# Power.net
KiCad netlist of a schematic drawn in Altium Designer
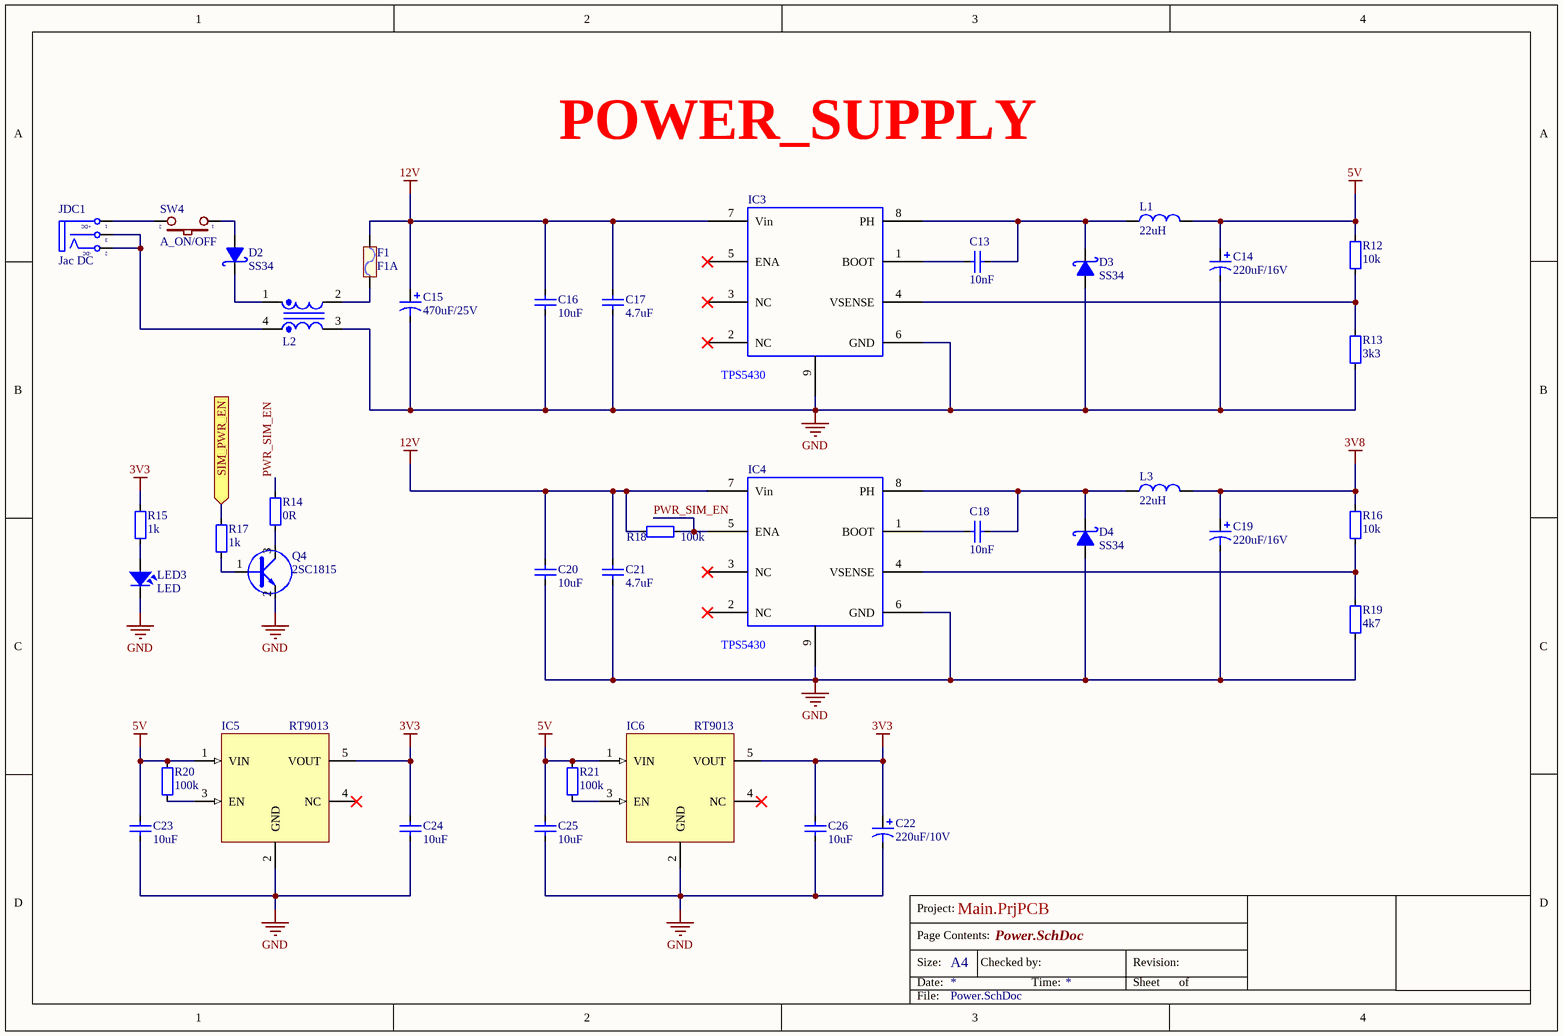
[diagram p0: Power.SchDoc]

(export (version "E")
  (design (tool "Eeschema 10.0.6"))
  (components
    (comp (ref "C13")
      (value "10nF")
      (footprint "CAP_0805")
      (description "Capacitor")
      (fields (field (name "PUBLISHER") "Altium Limited"))
      (libsource (lib "My Library") (part "CapSMD"))
    )
    (comp (ref "C14")
      (value "220uF/16V")
      (footprint "C8mm")
      (description "Polarized Capacitor (Axial)")
      (fields (field (name "PUBLISHER") "Altium Limited"))
      (libsource (lib "My Library") (part "Cap Pol"))
    )
    (comp (ref "C15")
      (value "470uF/25V")
      (footprint "C8mm")
      (description "Polarized Capacitor (Axial)")
      (fields (field (name "PUBLISHER") "Altium Limited"))
      (libsource (lib "My Library") (part "Cap Pol"))
    )
    (comp (ref "C16")
      (value "10uF")
      (footprint "CAP_0805")
      (description "Capacitor")
      (fields (field (name "PUBLISHER") "Altium Limited"))
      (libsource (lib "My Library") (part "CapSMD"))
    )
    (comp (ref "C17")
      (value "4.7uF")
      (footprint "CAP_0805")
      (description "Capacitor")
      (fields (field (name "PUBLISHER") "Altium Limited"))
      (libsource (lib "My Library") (part "CapSMD"))
    )
    (comp (ref "C18")
      (value "10nF")
      (footprint "CAP_0805")
      (description "Capacitor")
      (fields (field (name "PUBLISHER") "Altium Limited"))
      (libsource (lib "My Library") (part "CapSMD"))
    )
    (comp (ref "C19")
      (value "220uF/16V")
      (footprint "C8mm")
      (description "Polarized Capacitor (Axial)")
      (fields (field (name "PUBLISHER") "Altium Limited"))
      (libsource (lib "My Library") (part "Cap Pol"))
    )
    (comp (ref "C20")
      (value "10uF")
      (footprint "CAP_0805")
      (description "Capacitor")
      (fields (field (name "PUBLISHER") "Altium Limited"))
      (libsource (lib "My Library") (part "CapSMD"))
    )
    (comp (ref "C21")
      (value "4.7uF")
      (footprint "CAP_0805")
      (description "Capacitor")
      (fields (field (name "PUBLISHER") "Altium Limited"))
      (libsource (lib "My Library") (part "CapSMD"))
    )
    (comp (ref "C22")
      (value "220uF/10V")
      (footprint "C8mm")
      (description "Polarized Capacitor (Axial)")
      (fields (field (name "PUBLISHER") "Altium Limited"))
      (libsource (lib "My Library") (part "Cap Pol"))
    )
    (comp (ref "C23")
      (value "10uF")
      (footprint "CAP_0805")
      (description "Capacitor")
      (fields (field (name "PUBLISHER") "Altium Limited"))
      (libsource (lib "My Library") (part "CapSMD"))
    )
    (comp (ref "C24")
      (value "10uF")
      (footprint "CAP_0805")
      (description "Capacitor")
      (fields (field (name "PUBLISHER") "Altium Limited"))
      (libsource (lib "My Library") (part "CapSMD"))
    )
    (comp (ref "C25")
      (value "10uF")
      (footprint "CAP_0805")
      (description "Capacitor")
      (fields (field (name "PUBLISHER") "Altium Limited"))
      (libsource (lib "My Library") (part "CapSMD"))
    )
    (comp (ref "C26")
      (value "10uF")
      (footprint "CAP_0805")
      (description "Capacitor")
      (fields (field (name "PUBLISHER") "Altium Limited"))
      (libsource (lib "My Library") (part "CapSMD"))
    )
    (comp (ref "D2")
      (value "SS34")
      (footprint "DO-214AC(SMA)")
      (description "Diode Schottky SS34")
      (libsource (lib "My Library") (part "Diode Schottky"))
    )
    (comp (ref "D3")
      (value "SS34")
      (footprint "DO-214AC(SMA)")
      (description "Diode Schottky SS34")
      (libsource (lib "My Library") (part "Diode Schottky"))
    )
    (comp (ref "D4")
      (value "SS34")
      (footprint "DO-214AC(SMA)")
      (description "Diode Schottky SS34")
      (libsource (lib "My Library") (part "Diode Schottky"))
    )
    (comp (ref "F1")
      (value "F1A")
      (footprint "FUSE2C")
      (description "Fuse RUEF300 30V 3A")
      (fields (field (name "DESIGNED BY") "VanDungEvn"))
      (libsource (lib "My Library") (part "Fuse"))
    )
    (comp (ref "IC3")
      (value "TPS5430")
      (footprint "TPS5430-2")
      (fields (field (name "NAME") "TPS5430"))
      (libsource (lib "My Library") (part "TPS5430"))
    )
    (comp (ref "IC4")
      (value "TPS5430")
      (footprint "TPS5430-2")
      (fields (field (name "NAME") "TPS5430"))
      (libsource (lib "My Library") (part "TPS5430"))
    )
    (comp (ref "IC5")
      (value "RT9013")
      (footprint "SOT23-5")
      (description "RT9013-33GB IC REG LINEAR 3.3V 500mA SOT23-5")
      (libsource (lib "My Library") (part "RT9013"))
    )
    (comp (ref "IC6")
      (value "RT9013")
      (footprint "SOT23-5")
      (description "RT9013-33GB IC REG LINEAR 3.3V 500mA SOT23-5")
      (libsource (lib "My Library") (part "RT9013"))
    )
    (comp (ref "JDC1")
      (value "Jac DC")
      (footprint "DC-IN")
      (description "Jac DC input")
      (libsource (lib "My Library") (part "DCIN"))
    )
    (comp (ref "L1")
      (value "22uH")
      (footprint "L-SMD-M-7.3x4.5")
      (description "Inductor")
      (libsource (lib "My Library") (part "Inductor"))
    )
    (comp (ref "L2")
      (value "Inductor Filter")
      (footprint "EE8.3")
      (fields (field (name "DESIGNED BY") "VanDungEvn"))
      (libsource (lib "My Library") (part "L_Filter"))
    )
    (comp (ref "L3")
      (value "22uH")
      (footprint "L-SMD-M-7.3x4.5")
      (description "Inductor")
      (libsource (lib "My Library") (part "Inductor"))
    )
    (comp (ref "LED3")
      (value "LED")
      (footprint "LED-0805-Red")
      (description "LED Single colour Green and Red")
      (libsource (lib "My Library") (part "LED"))
    )
    (comp (ref "Q4")
      (value "2SC1815")
      (footprint "SOT23D")
      (description "NPN 600mW, ECB")
      (libsource (lib "My Library") (part "C1815"))
    )
    (comp (ref "R12")
      (value "10k")
      (footprint "RES-SMD-0805")
      (description "Resistor")
      (fields
        (field (name "MANUFACTURER") "Generic Components")
        (field (name "PUBLISHER") "Altium Hobart Technology Centre")
      )
      (libsource (lib "My Library") (part "Resistor - SMD"))
    )
    (comp (ref "R13")
      (value "3k3")
      (footprint "RES-SMD-0805")
      (description "Resistor")
      (fields
        (field (name "MANUFACTURER") "Generic Components")
        (field (name "PUBLISHER") "Altium Hobart Technology Centre")
      )
      (libsource (lib "My Library") (part "Resistor - SMD"))
    )
    (comp (ref "R14")
      (value "0R")
      (footprint "RES-SMD-0805")
      (description "Resistor")
      (fields
        (field (name "MANUFACTURER") "Generic Components")
        (field (name "PUBLISHER") "Altium Hobart Technology Centre")
      )
      (libsource (lib "My Library") (part "Resistor - SMD"))
    )
    (comp (ref "R15")
      (value "1k")
      (footprint "RES-SMD-0805")
      (description "Resistor")
      (fields
        (field (name "MANUFACTURER") "Generic Components")
        (field (name "PUBLISHER") "Altium Hobart Technology Centre")
      )
      (libsource (lib "My Library") (part "Resistor - SMD"))
    )
    (comp (ref "R16")
      (value "10k")
      (footprint "RES-SMD-0805")
      (description "Resistor")
      (fields
        (field (name "MANUFACTURER") "Generic Components")
        (field (name "PUBLISHER") "Altium Hobart Technology Centre")
      )
      (libsource (lib "My Library") (part "Resistor - SMD"))
    )
    (comp (ref "R17")
      (value "1k")
      (footprint "RES-SMD-0805")
      (description "Resistor")
      (fields
        (field (name "MANUFACTURER") "Generic Components")
        (field (name "PUBLISHER") "Altium Hobart Technology Centre")
      )
      (libsource (lib "My Library") (part "Resistor - SMD"))
    )
    (comp (ref "R18")
      (value "100k")
      (footprint "RES-SMD-0805")
      (description "Resistor")
      (fields
        (field (name "MANUFACTURER") "Generic Components")
        (field (name "PUBLISHER") "Altium Hobart Technology Centre")
      )
      (libsource (lib "My Library") (part "Resistor - SMD"))
    )
    (comp (ref "R19")
      (value "4k7")
      (footprint "RES-SMD-0805")
      (description "Resistor")
      (fields
        (field (name "MANUFACTURER") "Generic Components")
        (field (name "PUBLISHER") "Altium Hobart Technology Centre")
      )
      (libsource (lib "My Library") (part "Resistor - SMD"))
    )
    (comp (ref "R20")
      (value "100k")
      (footprint "RES-SMD-0805")
      (description "Resistor")
      (fields
        (field (name "MANUFACTURER") "Generic Components")
        (field (name "PUBLISHER") "Altium Hobart Technology Centre")
      )
      (libsource (lib "My Library") (part "Resistor - SMD"))
    )
    (comp (ref "R21")
      (value "100k")
      (footprint "RES-SMD-0805")
      (description "Resistor")
      (fields
        (field (name "MANUFACTURER") "Generic Components")
        (field (name "PUBLISHER") "Altium Hobart Technology Centre")
      )
      (libsource (lib "My Library") (part "Resistor - SMD"))
    )
    (comp (ref "SW4")
      (value "A_ON/OFF")
      (footprint "SW102_SIDE")
      (description "Switch button 2 pin")
      (libsource (lib "My Library") (part "SW2"))
    )
  )
  (nets
    (net (code "1") (name "/PWR_SIM_EN") (class "Default")
      (node (ref "IC4") (pin "5") (pinfunction "ENA_5") (pintype "passive"))
      (node (ref "R14") (pin "2") (pinfunction "2_2") (pintype "passive"))
      (node (ref "R18") (pin "1") (pinfunction "1_1") (pintype "passive"))
    )
    (net (code "2") (name "/SIM_PWR_EN") (class "Default")
      (node (ref "R17") (pin "2") (pinfunction "2_2") (pintype "passive"))
    )
    (net (code "3") (name "3V3") (class "Default")
      (node (ref "C22") (pin "1") (pinfunction "1_1") (pintype "passive"))
      (node (ref "C24") (pin "2") (pinfunction "2_2") (pintype "passive"))
      (node (ref "C26") (pin "2") (pinfunction "2_2") (pintype "passive"))
      (node (ref "IC5") (pin "5") (pinfunction "VOUT_5") (pintype "power_in"))
      (node (ref "IC6") (pin "5") (pinfunction "VOUT_5") (pintype "power_in"))
      (node (ref "R15") (pin "2") (pinfunction "2_2") (pintype "passive"))
    )
    (net (code "4") (name "3V8") (class "Default")
      (node (ref "C19") (pin "1") (pinfunction "1_1") (pintype "passive"))
      (node (ref "L3") (pin "2") (pinfunction "2_2") (pintype "passive"))
      (node (ref "R16") (pin "2") (pinfunction "2_2") (pintype "passive"))
    )
    (net (code "5") (name "5V") (class "Default")
      (node (ref "C14") (pin "1") (pinfunction "1_1") (pintype "passive"))
      (node (ref "C23") (pin "2") (pinfunction "2_2") (pintype "passive"))
      (node (ref "C25") (pin "2") (pinfunction "2_2") (pintype "passive"))
      (node (ref "IC5") (pin "1") (pinfunction "VIN_1") (pintype "input"))
      (node (ref "IC6") (pin "1") (pinfunction "VIN_1") (pintype "input"))
      (node (ref "L1") (pin "2") (pinfunction "2_2") (pintype "passive"))
      (node (ref "R12") (pin "2") (pinfunction "2_2") (pintype "passive"))
      (node (ref "R20") (pin "1") (pinfunction "1_1") (pintype "passive"))
      (node (ref "R21") (pin "1") (pinfunction "1_1") (pintype "passive"))
    )
    (net (code "6") (name "12V") (class "Default")
      (node (ref "C15") (pin "1") (pinfunction "1_1") (pintype "passive"))
      (node (ref "C16") (pin "2") (pinfunction "2_2") (pintype "passive"))
      (node (ref "C17") (pin "2") (pinfunction "2_2") (pintype "passive"))
      (node (ref "C20") (pin "2") (pinfunction "2_2") (pintype "passive"))
      (node (ref "C21") (pin "2") (pinfunction "2_2") (pintype "passive"))
      (node (ref "F1") (pin "2") (pinfunction "2_2") (pintype "passive"))
      (node (ref "IC3") (pin "7") (pinfunction "Vin_7") (pintype "passive"))
      (node (ref "IC4") (pin "7") (pinfunction "Vin_7") (pintype "passive"))
      (node (ref "R18") (pin "2") (pinfunction "2_2") (pintype "passive"))
    )
    (net (code "7") (name "GND") (class "Default")
      (node (ref "C14") (pin "2") (pinfunction "2_2") (pintype "passive"))
      (node (ref "C15") (pin "2") (pinfunction "2_2") (pintype "passive"))
      (node (ref "C16") (pin "1") (pinfunction "1_1") (pintype "passive"))
      (node (ref "C17") (pin "1") (pinfunction "1_1") (pintype "passive"))
      (node (ref "C19") (pin "2") (pinfunction "2_2") (pintype "passive"))
      (node (ref "C20") (pin "1") (pinfunction "1_1") (pintype "passive"))
      (node (ref "C21") (pin "1") (pinfunction "1_1") (pintype "passive"))
      (node (ref "C22") (pin "2") (pinfunction "2_2") (pintype "passive"))
      (node (ref "C23") (pin "1") (pinfunction "1_1") (pintype "passive"))
      (node (ref "C24") (pin "1") (pinfunction "1_1") (pintype "passive"))
      (node (ref "C25") (pin "1") (pinfunction "1_1") (pintype "passive"))
      (node (ref "C26") (pin "1") (pinfunction "1_1") (pintype "passive"))
      (node (ref "D3") (pin "1") (pinfunction "A_1") (pintype "passive"))
      (node (ref "D4") (pin "1") (pinfunction "A_1") (pintype "passive"))
      (node (ref "IC3") (pin "6") (pinfunction "GND_6") (pintype "passive"))
      (node (ref "IC3") (pin "9") (pinfunction "PWR_PAD_9") (pintype "passive"))
      (node (ref "IC4") (pin "6") (pinfunction "GND_6") (pintype "passive"))
      (node (ref "IC4") (pin "9") (pinfunction "PWR_PAD_9") (pintype "passive"))
      (node (ref "IC5") (pin "2") (pinfunction "GND_2") (pintype "passive"))
      (node (ref "IC6") (pin "2") (pinfunction "GND_2") (pintype "passive"))
      (node (ref "L2") (pin "3") (pintype "passive"))
      (node (ref "LED3") (pin "2") (pinfunction "2_2") (pintype "passive"))
      (node (ref "Q4") (pin "2") (pinfunction "E_2") (pintype "passive"))
      (node (ref "R13") (pin "1") (pinfunction "1_1") (pintype "passive"))
      (node (ref "R19") (pin "1") (pinfunction "1_1") (pintype "passive"))
    )
    (net (code "8") (name "Net-(D2-A)") (class "Default")
      (node (ref "D2") (pin "1") (pinfunction "A_1") (pintype "passive"))
      (node (ref "SW4") (pin "1") (pinfunction "1_1") (pintype "passive"))
    )
    (net (code "9") (name "Net-(D2-K)") (class "Default")
      (node (ref "D2") (pin "2") (pinfunction "K_2") (pintype "passive"))
      (node (ref "L2") (pin "1") (pintype "passive"))
    )
    (net (code "10") (name "Net-(D3-K)") (class "Default")
      (node (ref "C13") (pin "1") (pinfunction "1_1") (pintype "passive"))
      (node (ref "D3") (pin "2") (pinfunction "K_2") (pintype "passive"))
      (node (ref "IC3") (pin "8") (pinfunction "PH_8") (pintype "passive"))
      (node (ref "L1") (pin "1") (pinfunction "1_1") (pintype "passive"))
    )
    (net (code "11") (name "Net-(D4-K)") (class "Default")
      (node (ref "C18") (pin "1") (pinfunction "1_1") (pintype "passive"))
      (node (ref "D4") (pin "2") (pinfunction "K_2") (pintype "passive"))
      (node (ref "IC4") (pin "8") (pinfunction "PH_8") (pintype "passive"))
      (node (ref "L3") (pin "1") (pinfunction "1_1") (pintype "passive"))
    )
    (net (code "12") (name "Net-(F1-Pad1)") (class "Default")
      (node (ref "F1") (pin "1") (pinfunction "1_1") (pintype "passive"))
      (node (ref "L2") (pin "2") (pintype "passive"))
    )
    (net (code "13") (name "Net-(IC3-BOOT)") (class "Default")
      (node (ref "C13") (pin "2") (pinfunction "2_2") (pintype "passive"))
      (node (ref "IC3") (pin "1") (pinfunction "BOOT_1") (pintype "passive"))
    )
    (net (code "14") (name "Net-(IC3-VSENSE)") (class "Default")
      (node (ref "IC3") (pin "4") (pinfunction "VSENSE_4") (pintype "passive"))
      (node (ref "R12") (pin "1") (pinfunction "1_1") (pintype "passive"))
      (node (ref "R13") (pin "2") (pinfunction "2_2") (pintype "passive"))
    )
    (net (code "15") (name "Net-(IC4-BOOT)") (class "Default")
      (node (ref "C18") (pin "2") (pinfunction "2_2") (pintype "passive"))
      (node (ref "IC4") (pin "1") (pinfunction "BOOT_1") (pintype "passive"))
    )
    (net (code "16") (name "Net-(IC4-VSENSE)") (class "Default")
      (node (ref "IC4") (pin "4") (pinfunction "VSENSE_4") (pintype "passive"))
      (node (ref "R16") (pin "1") (pinfunction "1_1") (pintype "passive"))
      (node (ref "R19") (pin "2") (pinfunction "2_2") (pintype "passive"))
    )
    (net (code "17") (name "Net-(IC5-EN)") (class "Default")
      (node (ref "IC5") (pin "3") (pinfunction "EN_3") (pintype "input"))
      (node (ref "R20") (pin "2") (pinfunction "2_2") (pintype "passive"))
    )
    (net (code "18") (name "Net-(IC6-EN)") (class "Default")
      (node (ref "IC6") (pin "3") (pinfunction "EN_3") (pintype "input"))
      (node (ref "R21") (pin "2") (pinfunction "2_2") (pintype "passive"))
    )
    (net (code "19") (name "Net-(JDC1-S)") (class "Default")
      (node (ref "JDC1") (pin "2") (pinfunction "TN_2") (pintype "passive"))
      (node (ref "JDC1") (pin "3") (pinfunction "S_3") (pintype "power_in"))
      (node (ref "L2") (pin "4") (pintype "passive"))
    )
    (net (code "20") (name "Net-(JDC1-T)") (class "Default")
      (node (ref "JDC1") (pin "1") (pinfunction "T_1") (pintype "passive"))
      (node (ref "SW4") (pin "2") (pinfunction "2_2") (pintype "passive"))
    )
    (net (code "21") (name "Net-(LED3-Pad1)") (class "Default")
      (node (ref "LED3") (pin "1") (pinfunction "1_1") (pintype "passive"))
      (node (ref "R15") (pin "1") (pinfunction "1_1") (pintype "passive"))
    )
    (net (code "22") (name "Net-(Q4-B)") (class "Default")
      (node (ref "Q4") (pin "1") (pinfunction "B_1") (pintype "passive"))
      (node (ref "R17") (pin "1") (pinfunction "1_1") (pintype "passive"))
    )
    (net (code "23") (name "Net-(Q4-C)") (class "Default")
      (node (ref "Q4") (pin "3") (pinfunction "C_3") (pintype "passive"))
      (node (ref "R14") (pin "1") (pinfunction "1_1") (pintype "passive"))
    )
    (net (code "24") (name "unconnected-(IC3-ENA-Pad5)") (class "Default")
      (node (ref "IC3") (pin "5") (pinfunction "ENA_5") (pintype "passive+no_connect"))
    )
    (net (code "25") (name "unconnected-(IC3-NC-Pad2)") (class "Default")
      (node (ref "IC3") (pin "2") (pinfunction "NC_2") (pintype "passive+no_connect"))
    )
    (net (code "26") (name "unconnected-(IC3-NC-Pad3)") (class "Default")
      (node (ref "IC3") (pin "3") (pinfunction "NC_3") (pintype "passive+no_connect"))
    )
    (net (code "27") (name "unconnected-(IC4-NC-Pad2)") (class "Default")
      (node (ref "IC4") (pin "2") (pinfunction "NC_2") (pintype "passive+no_connect"))
    )
    (net (code "28") (name "unconnected-(IC4-NC-Pad3)") (class "Default")
      (node (ref "IC4") (pin "3") (pinfunction "NC_3") (pintype "passive+no_connect"))
    )
    (net (code "29") (name "unconnected-(IC5-NC-Pad4)") (class "Default")
      (node (ref "IC5") (pin "4") (pinfunction "NC_4") (pintype "passive+no_connect"))
    )
    (net (code "30") (name "unconnected-(IC6-NC-Pad4)") (class "Default")
      (node (ref "IC6") (pin "4") (pinfunction "NC_4") (pintype "passive+no_connect"))
    )
  )
)
